# Onlab.net
KiCad netlist of a schematic drawn in Altium Designer
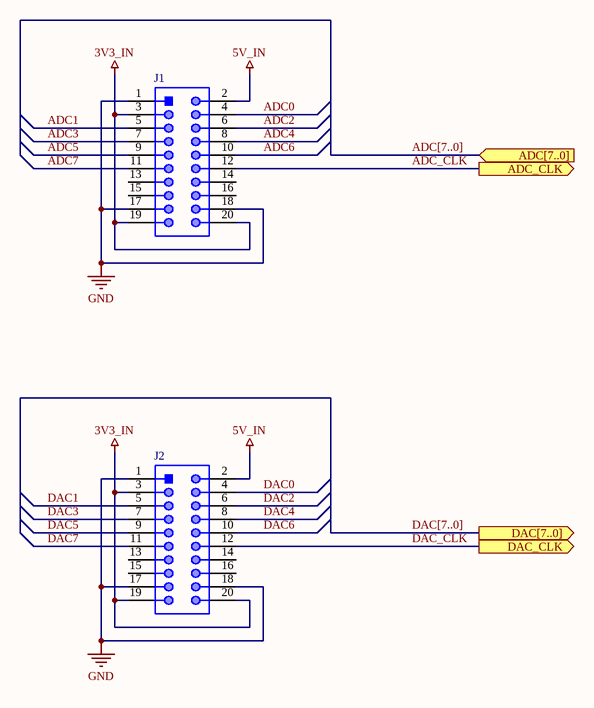
[diagram p0: Onlab.SchDoc]

(export (version "E")
  (design (tool "Eeschema 10.0.6"))
  (components
    (comp (ref "J1")
      (value "61302021021")
      (footprint "61302021021")
      (description "THT Angled Pin Header WR-PHD, Pitch 2.54 mm, Dual Row, 20 pins")
      (fields (field (name "MANUFACTURER") "Wurth Elektronik") (field (name "PUBLISHER") "WurthElektronik"))
      (libsource (lib "Altium Content Vault") (part "WE-CN-2P-M-R20"))
    )
    (comp (ref "J2")
      (value "61302021021")
      (footprint "61302021021")
      (description "THT Angled Pin Header WR-PHD, Pitch 2.54 mm, Dual Row, 20 pins")
      (fields (field (name "MANUFACTURER") "Wurth Elektronik") (field (name "PUBLISHER") "WurthElektronik"))
      (libsource (lib "Altium Content Vault") (part "WE-CN-2P-M-R20"))
    )
  )
  (nets
    (net (code "1") (name "/ADC0") (class "Default")
      (node (ref "J1") (pin "4") (pinfunction "4_4") (pintype "passive"))
    )
    (net (code "2") (name "/ADC1") (class "Default")
      (node (ref "J1") (pin "5") (pinfunction "5_5") (pintype "passive"))
    )
    (net (code "3") (name "/ADC2") (class "Default")
      (node (ref "J1") (pin "6") (pinfunction "6_6") (pintype "passive"))
    )
    (net (code "4") (name "/ADC3") (class "Default")
      (node (ref "J1") (pin "7") (pinfunction "7_7") (pintype "passive"))
    )
    (net (code "5") (name "/ADC4") (class "Default")
      (node (ref "J1") (pin "8") (pinfunction "8_8") (pintype "passive"))
    )
    (net (code "6") (name "/ADC5") (class "Default")
      (node (ref "J1") (pin "9") (pinfunction "9_9") (pintype "passive"))
    )
    (net (code "7") (name "/ADC6") (class "Default")
      (node (ref "J1") (pin "10") (pinfunction "10_10") (pintype "passive"))
    )
    (net (code "8") (name "/ADC7") (class "Default")
      (node (ref "J1") (pin "11") (pinfunction "11_11") (pintype "passive"))
    )
    (net (code "10") (name "/ADC_CLK") (class "Default")
      (node (ref "J1") (pin "12") (pinfunction "12_12") (pintype "passive"))
    )
    (net (code "11") (name "/DAC0") (class "Default")
      (node (ref "J2") (pin "4") (pinfunction "4_4") (pintype "passive"))
    )
    (net (code "12") (name "/DAC1") (class "Default")
      (node (ref "J2") (pin "5") (pinfunction "5_5") (pintype "passive"))
    )
    (net (code "13") (name "/DAC2") (class "Default")
      (node (ref "J2") (pin "6") (pinfunction "6_6") (pintype "passive"))
    )
    (net (code "14") (name "/DAC3") (class "Default")
      (node (ref "J2") (pin "7") (pinfunction "7_7") (pintype "passive"))
    )
    (net (code "15") (name "/DAC4") (class "Default")
      (node (ref "J2") (pin "8") (pinfunction "8_8") (pintype "passive"))
    )
    (net (code "16") (name "/DAC5") (class "Default")
      (node (ref "J2") (pin "9") (pinfunction "9_9") (pintype "passive"))
    )
    (net (code "17") (name "/DAC6") (class "Default")
      (node (ref "J2") (pin "10") (pinfunction "10_10") (pintype "passive"))
    )
    (net (code "18") (name "/DAC7") (class "Default")
      (node (ref "J2") (pin "11") (pinfunction "11_11") (pintype "passive"))
    )
    (net (code "20") (name "/DAC_CLK") (class "Default")
      (node (ref "J2") (pin "12") (pinfunction "12_12") (pintype "passive"))
    )
    (net (code "21") (name "3V3_IN") (class "Default")
      (node (ref "J1") (pin "19") (pinfunction "19_19") (pintype "passive"))
      (node (ref "J1") (pin "20") (pinfunction "20_20") (pintype "passive"))
      (node (ref "J1") (pin "3") (pinfunction "3_3") (pintype "passive"))
      (node (ref "J2") (pin "19") (pinfunction "19_19") (pintype "passive"))
      (node (ref "J2") (pin "20") (pinfunction "20_20") (pintype "passive"))
      (node (ref "J2") (pin "3") (pinfunction "3_3") (pintype "passive"))
    )
    (net (code "22") (name "5V_IN") (class "Default")
      (node (ref "J1") (pin "2") (pinfunction "2_2") (pintype "passive"))
      (node (ref "J2") (pin "2") (pinfunction "2_2") (pintype "passive"))
    )
    (net (code "23") (name "GND") (class "Default")
      (node (ref "J1") (pin "1") (pinfunction "1_1") (pintype "passive"))
      (node (ref "J1") (pin "17") (pinfunction "17_17") (pintype "passive"))
      (node (ref "J1") (pin "18") (pinfunction "18_18") (pintype "passive"))
      (node (ref "J2") (pin "1") (pinfunction "1_1") (pintype "passive"))
      (node (ref "J2") (pin "17") (pinfunction "17_17") (pintype "passive"))
      (node (ref "J2") (pin "18") (pinfunction "18_18") (pintype "passive"))
    )
    (net (code "24") (name "unconnected-(J1-Pad13)") (class "Default")
      (node (ref "J1") (pin "13") (pinfunction "13_13") (pintype "passive"))
    )
    (net (code "25") (name "unconnected-(J1-Pad14)") (class "Default")
      (node (ref "J1") (pin "14") (pinfunction "14_14") (pintype "passive"))
    )
    (net (code "26") (name "unconnected-(J1-Pad15)") (class "Default")
      (node (ref "J1") (pin "15") (pinfunction "15_15") (pintype "passive"))
    )
    (net (code "27") (name "unconnected-(J1-Pad16)") (class "Default")
      (node (ref "J1") (pin "16") (pinfunction "16_16") (pintype "passive"))
    )
    (net (code "28") (name "unconnected-(J2-Pad13)") (class "Default")
      (node (ref "J2") (pin "13") (pinfunction "13_13") (pintype "passive"))
    )
    (net (code "29") (name "unconnected-(J2-Pad14)") (class "Default")
      (node (ref "J2") (pin "14") (pinfunction "14_14") (pintype "passive"))
    )
    (net (code "30") (name "unconnected-(J2-Pad15)") (class "Default")
      (node (ref "J2") (pin "15") (pinfunction "15_15") (pintype "passive"))
    )
    (net (code "31") (name "unconnected-(J2-Pad16)") (class "Default")
      (node (ref "J2") (pin "16") (pinfunction "16_16") (pintype "passive"))
    )
  )
)
